# Sheet1.net
KiCad netlist of a schematic drawn in Altium Designer
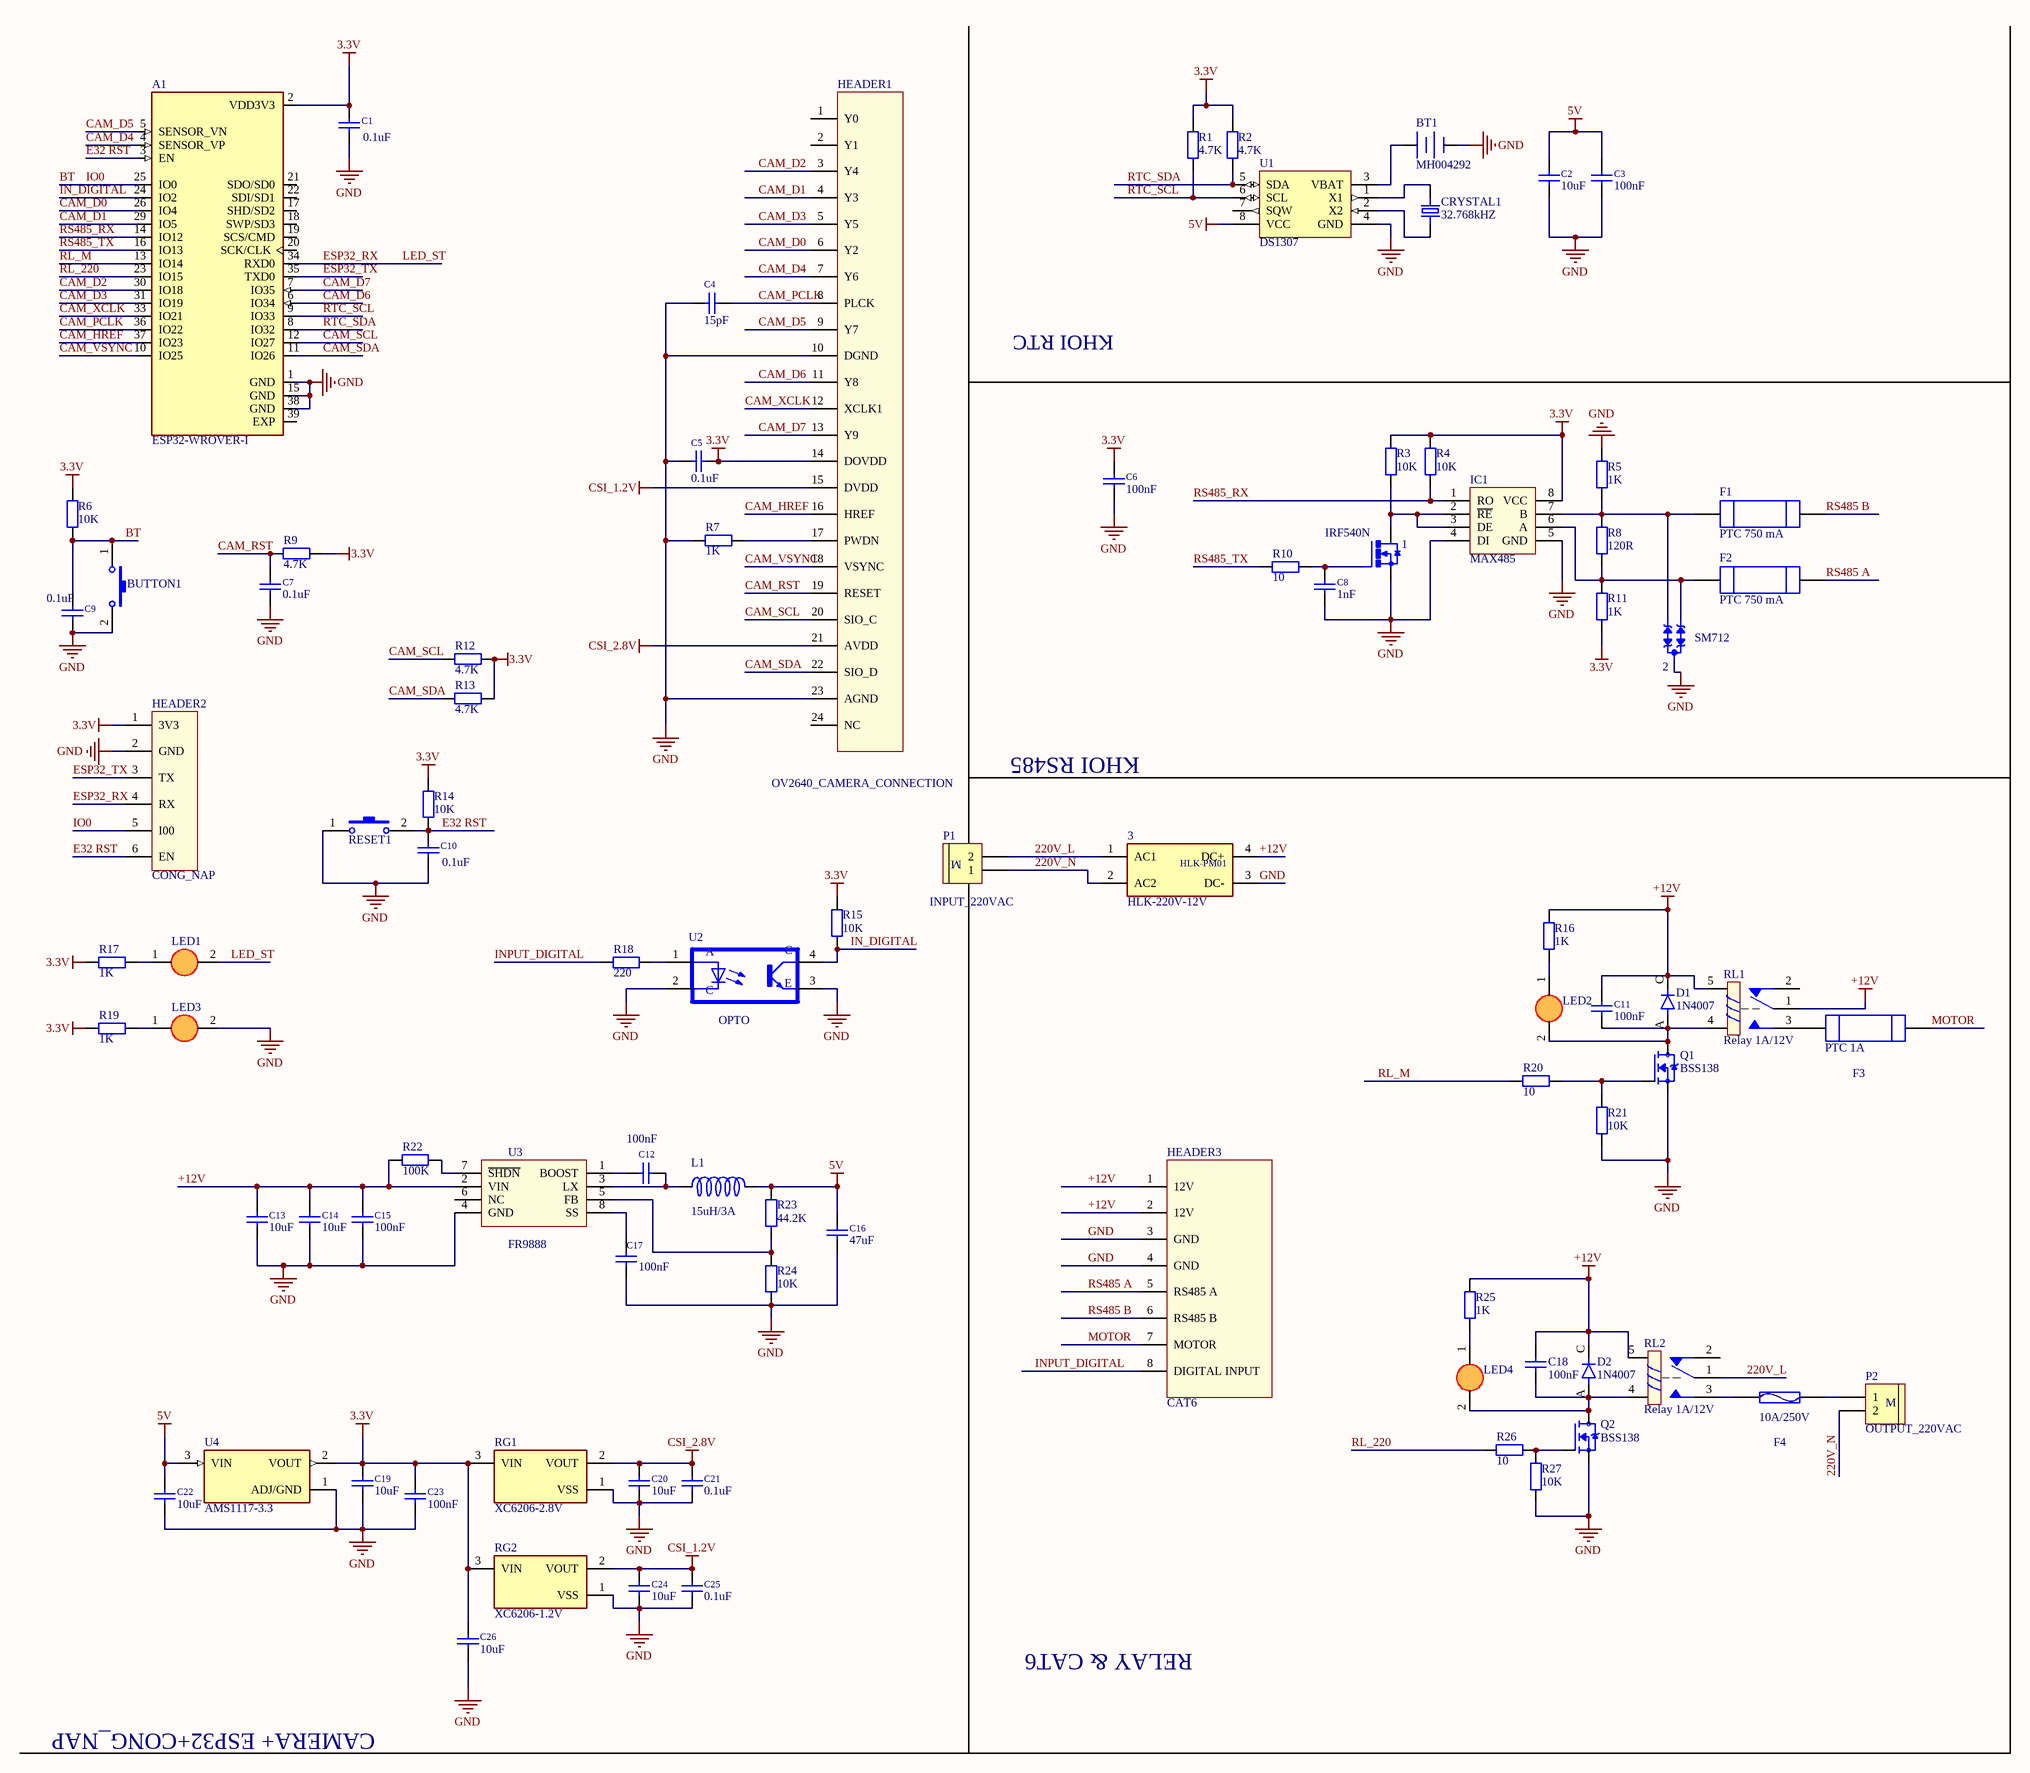
[diagram p0: Sheet1.SchDoc]

(export (version "E")
  (design (tool "Eeschema 10.0.6"))
  (components
    (comp (ref "1")
      (value "IRF540N")
      (footprint "D2PACK")
      (description "N-Channel 100V 33A _Tc_ 130W _Tc_ Surface Mount D2PAK")
      (fields (field (name "MF") "Infineon Technologies"))
      (libsource (lib "IRF540N") (part "IRF540N"))
    )
    (comp (ref "2")
      (value "SM712")
      (footprint "SOT23-3")
      (description "26V, 14V Clamp 17A _8/20Âµs_ Ipp Tvs Diode Surface Mount SOT-23-3")
      (fields (field (name "MP") "CDSOT23-SM712") (field (name "MF") "Bourns"))
      (libsource (lib "CDSOT23-SM712") (part "CDSOT23-SM712"))
    )
    (comp (ref "3")
      (value "HLK-220V-12V")
      (footprint "HLK 220-12")
      (fields (field (name "MF") "Hi-link") (field (name "MP") "hlk-pm01"))
      (libsource (lib "HLK-PM01") (part "HLK-PM01"))
    )
    (comp (ref "A1")
      (value "ESP32-WROVER-I")
      (footprint "XCVR_ESP32-WROVER-I")
      (fields (field (name "MF") "Espressif Systems"))
      (libsource (lib "ESP32-WROVER-I") (part "ESP32-WROVER-I"))
    )
    (comp (ref "BT1")
      (value "MH004292")
      (footprint "DE PINCR1220")
      (description "Dán")
      (libsource (lib "THU VIEN SCH") (part "De Pin 3.3V"))
    )
    (comp (ref "BUTTON1")
      (value "SW-2P-S")
      (footprint "BUTTON_4_PIN")
      (description "Switch Small 2 Pin")
      (fields (field (name "PUBLISHER") "Altium Limited"))
      (libsource (lib "Schematic") (part "SW-2PIN-SMALL"))
    )
    (comp (ref "C1")
      (value "0.1uF")
      (footprint "Tu 0603")
      (description "Capacitor")
      (fields (field (name "PUBLISHER") "Hoang Nguyen"))
      (libsource (lib "hphonglib") (part "Capacitor"))
    )
    (comp (ref "C2")
      (value "10uF")
      (footprint "C1210")
      (description "Capacitor")
      (fields (field (name "PUBLISHER") "Hoang Nguyen"))
      (libsource (lib "hphonglib") (part "Capacitor"))
    )
    (comp (ref "C3")
      (value "100nF")
      (footprint "Tu 0603")
      (description "Capacitor")
      (fields (field (name "PUBLISHER") "Hoang Nguyen"))
      (libsource (lib "hphonglib") (part "Capacitor"))
    )
    (comp (ref "C4")
      (value "15pF")
      (footprint "Tu 0603")
      (description "Capacitor")
      (fields (field (name "PUBLISHER") "Hoang Nguyen"))
      (libsource (lib "hphonglib") (part "Capacitor"))
    )
    (comp (ref "C5")
      (value "0.1uF")
      (footprint "Tu 0603")
      (description "Capacitor")
      (fields (field (name "PUBLISHER") "Hoang Nguyen"))
      (libsource (lib "hphonglib") (part "Capacitor"))
    )
    (comp (ref "C6")
      (value "100nF")
      (footprint "Tu 0603")
      (description "Capacitor")
      (fields (field (name "PUBLISHER") "Hoang Nguyen"))
      (libsource (lib "hphonglib") (part "Capacitor"))
    )
    (comp (ref "C7")
      (value "0.1uF")
      (footprint "Tu 0603")
      (description "Capacitor")
      (fields (field (name "PUBLISHER") "Hoang Nguyen"))
      (libsource (lib "hphonglib") (part "Capacitor"))
    )
    (comp (ref "C8")
      (value "1nF")
      (footprint "Tu 0603")
      (description "Capacitor")
      (fields (field (name "PUBLISHER") "Hoang Nguyen"))
      (libsource (lib "hphonglib") (part "Capacitor"))
    )
    (comp (ref "C9")
      (value "0.1uF")
      (footprint "Tu 0603")
      (description "Capacitor")
      (fields (field (name "PUBLISHER") "Hoang Nguyen"))
      (libsource (lib "hphonglib") (part "Capacitor"))
    )
    (comp (ref "C10")
      (value "0.1uF")
      (footprint "Tu 0603")
      (description "Capacitor")
      (fields (field (name "PUBLISHER") "Hoang Nguyen"))
      (libsource (lib "hphonglib") (part "Capacitor"))
    )
    (comp (ref "C11")
      (value "100nF")
      (footprint "Tu 0603")
      (description "Capacitor")
      (fields (field (name "PUBLISHER") "Hoang Nguyen"))
      (libsource (lib "hphonglib") (part "Capacitor"))
    )
    (comp (ref "C12")
      (value "100nF")
      (footprint "Tu 0603")
      (description "Capacitor")
      (fields (field (name "PUBLISHER") "Hoang Nguyen"))
      (libsource (lib "hphonglib") (part "Capacitor"))
    )
    (comp (ref "C13")
      (value "10uF")
      (footprint "C1210")
      (description "Capacitor")
      (fields (field (name "PUBLISHER") "Hoang Nguyen"))
      (libsource (lib "hphonglib") (part "Capacitor"))
    )
    (comp (ref "C14")
      (value "10uF")
      (footprint "C1210")
      (description "Capacitor")
      (fields (field (name "PUBLISHER") "Hoang Nguyen"))
      (libsource (lib "hphonglib") (part "Capacitor"))
    )
    (comp (ref "C15")
      (value "100nF")
      (footprint "Tu 0603")
      (description "Capacitor")
      (fields (field (name "PUBLISHER") "Hoang Nguyen"))
      (libsource (lib "hphonglib") (part "Capacitor"))
    )
    (comp (ref "C16")
      (value "47uF")
      (footprint "C1210")
      (description "Capacitor")
      (fields (field (name "PUBLISHER") "Hoang Nguyen"))
      (libsource (lib "hphonglib") (part "Capacitor"))
    )
    (comp (ref "C17")
      (value "100nF")
      (footprint "Tu 0603")
      (description "Capacitor")
      (fields (field (name "PUBLISHER") "Hoang Nguyen"))
      (libsource (lib "hphonglib") (part "Capacitor"))
    )
    (comp (ref "C18")
      (value "100nF")
      (footprint "Tu 0603")
      (libsource (lib "Schematic") (part "Cap SMD 1206"))
    )
    (comp (ref "C19")
      (value "10uF")
      (footprint "C1210")
      (description "Capacitor")
      (fields (field (name "PUBLISHER") "Hoang Nguyen"))
      (libsource (lib "hphonglib") (part "Capacitor"))
    )
    (comp (ref "C20")
      (value "10uF")
      (footprint "C1210")
      (description "Capacitor")
      (fields (field (name "PUBLISHER") "Hoang Nguyen"))
      (libsource (lib "hphonglib") (part "Capacitor"))
    )
    (comp (ref "C21")
      (value "0.1uF")
      (footprint "Tu 0603")
      (description "Capacitor")
      (fields (field (name "PUBLISHER") "Hoang Nguyen"))
      (libsource (lib "hphonglib") (part "Capacitor"))
    )
    (comp (ref "C22")
      (value "10uF")
      (footprint "C1210")
      (description "Capacitor")
      (fields (field (name "PUBLISHER") "Hoang Nguyen"))
      (libsource (lib "hphonglib") (part "Capacitor"))
    )
    (comp (ref "C23")
      (value "100nF")
      (footprint "Tu 0603")
      (description "Capacitor")
      (fields (field (name "PUBLISHER") "Hoang Nguyen"))
      (libsource (lib "hphonglib") (part "Capacitor"))
    )
    (comp (ref "C24")
      (value "10uF")
      (footprint "C1210")
      (description "Capacitor")
      (fields (field (name "PUBLISHER") "Hoang Nguyen"))
      (libsource (lib "hphonglib") (part "Capacitor"))
    )
    (comp (ref "C25")
      (value "0.1uF")
      (footprint "Tu 0603")
      (description "Capacitor")
      (fields (field (name "PUBLISHER") "Hoang Nguyen"))
      (libsource (lib "hphonglib") (part "Capacitor"))
    )
    (comp (ref "C26")
      (value "10uF")
      (footprint "C1210")
      (description "Capacitor")
      (fields (field (name "PUBLISHER") "Hoang Nguyen"))
      (libsource (lib "hphonglib") (part "Capacitor"))
    )
    (comp (ref "CRYSTAL1")
      (value "32.768kHZ")
      (footprint "XTAL_ABS07-32.768KHZ-T")
      (description "32.768kHz Â±20ppm Crystal 12.5pF 70 kOhms 2-SMD, No Lead")
      (fields (field (name "MF") "Abracon LLC") (field (name "MP") "ABS07-32.768KHZ"))
      (libsource (lib "ABS07-32.768KHZ-T") (part "ABS07-32.768KHZ-T"))
    )
    (comp (ref "D1")
      (value "1N4007")
      (footprint "DIOAD1060W80L520D270")
      (description "Diode Standard 1000V 1A Through Hole DO-204AL _DO-41_")
      (fields (field (name "MF") "ON Semiconductor"))
      (libsource (lib "1N4007") (part "1N4007"))
    )
    (comp (ref "D2")
      (value "1N4007")
      (footprint "DIOAD1060W80L520D270")
      (description "Diode Standard 1000V 1A Through Hole DO-204AL _DO-41_")
      (fields (field (name "MF") "ON Semiconductor"))
      (libsource (lib "1N4007") (part "1N4007"))
    )
    (comp (ref "F1")
      (value "PTC 750 mA")
      (footprint "1812")
      (description "Polymeric PTC Resettable Fuse 13.2V 750mA Ih Surface Mount 1812 _4532 Metric_, Concave")
      (fields (field (name "MP") "1812L075PR") (field (name "MF") "Littelfuse Inc."))
      (libsource (lib "PTC750mA") (part "1812L075PR"))
    )
    (comp (ref "F2")
      (value "PTC 750 mA")
      (footprint "1812")
      (description "Polymeric PTC Resettable Fuse 13.2V 750mA Ih Surface Mount 1812 _4532 Metric_, Concave")
      (fields (field (name "MP") "1812L075PR") (field (name "MF") "Littelfuse Inc."))
      (libsource (lib "PTC750mA") (part "1812L075PR"))
    )
    (comp (ref "F3")
      (value "PTC 1A")
      (footprint "1812")
      (description "Polymeric PTC Resettable Fuse 13.2V 750mA Ih Surface Mount 1812 _4532 Metric_, Concave")
      (fields (field (name "MP") "1812L075PR") (field (name "MF") "Littelfuse Inc."))
      (libsource (lib "PTC750mA") (part "1812L075PR"))
    )
    (comp (ref "F4")
      (value "10A/250V")
      (footprint "FUSE_10A")
      (description "Fuse")
      (fields (field (name "PUBLISHER") "Altium Limited"))
      (libsource (lib "Schematic") (part "Fuse 1"))
    )
    (comp (ref "HEADER1")
      (value "OV2640_CAMERA_CONNECTION")
      (footprint "OV2640_0.5mm")
      (description "OV2640_CAMERA")
      (libsource (lib "NGUYENVY08") (part "OV2640_CAMERA"))
    )
    (comp (ref "HEADER2")
      (value "CONG_NAP")
      (footprint "CONG_NAP")
      (libsource (lib "NGUYENVY08") (part "HEADER_6"))
    )
    (comp (ref "HEADER3")
      (value "CAT6")
      (footprint "CAT6_3.5mm")
      (libsource (lib "NGUYENVY08") (part "CAT6"))
    )
    (comp (ref "IC1")
      (value "MAX485")
      (footprint "SO-8")
      (description "RS232 - RS485 (Same sn75176)")
      (libsource (lib "syhaunguyen") (part "MAX485"))
    )
    (comp (ref "L1")
      (value "15uH/3A")
      (footprint "CUON CAM 200mil")
      (libsource (lib "Schematic") (part "Conductor"))
    )
    (comp (ref "LED1")
      (value "~")
      (footprint "LED_SMD_0603 - duplicate1")
      (description "LED 5mm")
      (libsource (lib "Schematic") (part "LED 5mm"))
    )
    (comp (ref "LED2")
      (value "~")
      (footprint "LED_SMD_0603 - duplicate1")
      (description "LED 5mm")
      (libsource (lib "Schematic") (part "LED 5mm"))
    )
    (comp (ref "LED3")
      (value "~")
      (footprint "LED_SMD_0603 - duplicate1")
      (description "LED 5mm")
      (libsource (lib "Schematic") (part "LED 5mm"))
    )
    (comp (ref "LED4")
      (value "~")
      (footprint "LED_SMD_0603 - duplicate1")
      (description "LED 5mm")
      (libsource (lib "Schematic") (part "LED 5mm"))
    )
    (comp (ref "P1")
      (value "INPUT_220VAC")
      (footprint "Medium - Header 2")
      (description "Header, 2-Pin, Medium")
      (fields (field (name "PUBLISHER") "Altium Limited"))
      (libsource (lib "Schematic") (part "Header 2 - M"))
    )
    (comp (ref "P2")
      (value "OUTPUT_220VAC")
      (footprint "Medium - Header 2")
      (description "Header, 2-Pin, Medium")
      (fields (field (name "PUBLISHER") "Altium Limited"))
      (libsource (lib "") (part "Header 2 - M_1"))
    )
    (comp (ref "Q1")
      (value "BSS138")
      (footprint "SOT95P240X111-3N")
      (description "N-Channel 50V 220mA (Ta) 360mW (Ta) Surface Mount SOT-23-3")
      (fields (field (name "MF") "MICROSS/On Semiconductor"))
      (libsource (lib "BSS138") (part "BSS138"))
    )
    (comp (ref "Q2")
      (value "BSS138")
      (footprint "SOT95P240X111-3N")
      (description "N-Channel 50V 220mA (Ta) 360mW (Ta) Surface Mount SOT-23-3")
      (fields (field (name "MF") "MICROSS/On Semiconductor"))
      (libsource (lib "BSS138") (part "BSS138"))
    )
    (comp (ref "R1")
      (value "4.7K")
      (footprint "TRO SMD 0603")
      (description "RES_08")
      (fields (field (name "PUBLISHER") "Altium Limited"))
      (libsource (lib "") (part "RES_08_1"))
    )
    (comp (ref "R2")
      (value "4.7K")
      (footprint "TRO SMD 0603")
      (description "RES_08")
      (fields (field (name "PUBLISHER") "Altium Limited"))
      (libsource (lib "") (part "RES_08_1"))
    )
    (comp (ref "R3")
      (value "10K")
      (footprint "TRO SMD 0603")
      (description "RES_08")
      (fields (field (name "PUBLISHER") "Altium Limited"))
      (libsource (lib "") (part "RES_08_1"))
    )
    (comp (ref "R4")
      (value "10K")
      (footprint "TRO SMD 0603")
      (description "RES_08")
      (fields (field (name "PUBLISHER") "Altium Limited"))
      (libsource (lib "") (part "RES_08_1"))
    )
    (comp (ref "R5")
      (value "1K")
      (footprint "TRO SMD 0603")
      (description "RES_08")
      (fields (field (name "PUBLISHER") "Altium Limited"))
      (libsource (lib "") (part "RES_08_1"))
    )
    (comp (ref "R6")
      (value "10K")
      (footprint "DIEN TRO 0805")
      (description "RES_08")
      (fields (field (name "PUBLISHER") "Altium Limited"))
      (libsource (lib "") (part "RES_08_1"))
    )
    (comp (ref "R7")
      (value "1K")
      (footprint "TRO SMD 0603")
      (description "RES_08")
      (fields (field (name "PUBLISHER") "Altium Limited"))
      (libsource (lib "Schematic") (part "RES_08"))
    )
    (comp (ref "R8")
      (value "120R")
      (footprint "TRO SMD 0603")
      (description "RES_08")
      (fields (field (name "PUBLISHER") "Altium Limited"))
      (libsource (lib "") (part "RES_08_1"))
    )
    (comp (ref "R9")
      (value "4.7K")
      (footprint "TRO SMD 0603")
      (description "RES_08")
      (fields (field (name "PUBLISHER") "Altium Limited"))
      (libsource (lib "Schematic") (part "RES_08"))
    )
    (comp (ref "R10")
      (value "10")
      (footprint "TRO SMD 0603")
      (description "RES_08")
      (fields (field (name "PUBLISHER") "Altium Limited"))
      (libsource (lib "") (part "RES_08_2"))
    )
    (comp (ref "R11")
      (value "1K")
      (footprint "TRO SMD 0603")
      (description "RES_08")
      (fields (field (name "PUBLISHER") "Altium Limited"))
      (libsource (lib "") (part "RES_08_1"))
    )
    (comp (ref "R12")
      (value "4.7K")
      (footprint "TRO SMD 0603")
      (description "RES_08")
      (fields (field (name "PUBLISHER") "Altium Limited"))
      (libsource (lib "Schematic") (part "RES_08"))
    )
    (comp (ref "R13")
      (value "4.7K")
      (footprint "TRO SMD 0603")
      (description "RES_08")
      (fields (field (name "PUBLISHER") "Altium Limited"))
      (libsource (lib "Schematic") (part "RES_08"))
    )
    (comp (ref "R14")
      (value "10K")
      (footprint "TRO SMD 0603")
      (description "RES_08")
      (fields (field (name "PUBLISHER") "Altium Limited"))
      (libsource (lib "") (part "RES_08_3"))
    )
    (comp (ref "R15")
      (value "10K")
      (footprint "TRO SMD 0603")
      (description "RES_08")
      (fields (field (name "PUBLISHER") "Altium Limited"))
      (libsource (lib "") (part "RES_08_1"))
    )
    (comp (ref "R16")
      (value "1K")
      (footprint "TRO SMD 0603")
      (description "RES_08")
      (fields (field (name "PUBLISHER") "Altium Limited"))
      (libsource (lib "") (part "RES_08_3"))
    )
    (comp (ref "R17")
      (value "1K")
      (footprint "TRO SMD 0603")
      (description "RES_08")
      (fields (field (name "PUBLISHER") "Altium Limited"))
      (libsource (lib "Schematic") (part "RES_08"))
    )
    (comp (ref "R18")
      (value "220")
      (footprint "TRO SMD 0603")
      (description "RES_08")
      (fields (field (name "PUBLISHER") "Altium Limited"))
      (libsource (lib "Schematic") (part "RES_08"))
    )
    (comp (ref "R19")
      (value "1K")
      (footprint "TRO SMD 0603")
      (description "RES_08")
      (fields (field (name "PUBLISHER") "Altium Limited"))
      (libsource (lib "Schematic") (part "RES_08"))
    )
    (comp (ref "R20")
      (value "10")
      (footprint "TRO SMD 0603")
      (description "RES_08")
      (fields (field (name "PUBLISHER") "Altium Limited"))
      (libsource (lib "") (part "RES_08_2"))
    )
    (comp (ref "R21")
      (value "10K")
      (footprint "TRO SMD 0603")
      (description "RES_08")
      (fields (field (name "PUBLISHER") "Altium Limited"))
      (libsource (lib "") (part "RES_08_1"))
    )
    (comp (ref "R22")
      (value "100K")
      (footprint "TRO SMD 0603")
      (description "RES_08")
      (fields (field (name "PUBLISHER") "Altium Limited"))
      (libsource (lib "Schematic") (part "RES_08"))
    )
    (comp (ref "R23")
      (value "44.2K")
      (footprint "DIEN TRO 0805")
      (description "RES_08")
      (fields (field (name "PUBLISHER") "Altium Limited"))
      (libsource (lib "") (part "RES_08_1"))
    )
    (comp (ref "R24")
      (value "10K")
      (footprint "TRO SMD 0603")
      (description "RES_08")
      (fields (field (name "PUBLISHER") "Altium Limited"))
      (libsource (lib "") (part "RES_08_1"))
    )
    (comp (ref "R25")
      (value "1K")
      (footprint "TRO SMD 0603")
      (description "RES_08")
      (fields (field (name "PUBLISHER") "Altium Limited"))
      (libsource (lib "") (part "RES_08_3"))
    )
    (comp (ref "R26")
      (value "10")
      (footprint "TRO SMD 0603")
      (description "RES_08")
      (fields (field (name "PUBLISHER") "Altium Limited"))
      (libsource (lib "") (part "RES_08_2"))
    )
    (comp (ref "R27")
      (value "10K")
      (footprint "TRO SMD 0603")
      (description "RES_08")
      (fields (field (name "PUBLISHER") "Altium Limited"))
      (libsource (lib "") (part "RES_08_1"))
    )
    (comp (ref "RESET1")
      (value "SW-2P-S")
      (footprint "BUTTON_4_PIN")
      (description "Switch Small 2 Pin")
      (fields (field (name "PUBLISHER") "Altium Limited"))
      (libsource (lib "Schematic") (part "SW-2PIN-SMALL"))
    )
    (comp (ref "RG1")
      (value "Reg_Torex_XC6206P332MR_eec")
      (footprint "Torex_https--www.torexsemi.com-file-SOT-23-SOT-23-pkg.pdf_0")
      (fields
        (field (name "PART NUMBER") "XC6206-2.8V")
        (field (name "VOLTAGE") "3.3V")
        (field (name "MANUFACTURER") "Torex")
        (field (name "MOUSER PART NUMBER") "865-XC6206P332MR-G")
      )
      (libsource (lib "Reg_Torex_XC6206P332MR_eec") (part "Reg_Torex_XC6206P332MR_eec"))
    )
    (comp (ref "RG2")
      (value "Reg_Torex_XC6206P332MR_eec")
      (footprint "Torex_https--www.torexsemi.com-file-SOT-23-SOT-23-pkg.pdf_0")
      (fields
        (field (name "PART NUMBER") "XC6206-1.2V")
        (field (name "VOLTAGE") "3.3V")
        (field (name "MANUFACTURER") "Torex")
        (field (name "MOUSER PART NUMBER") "865-XC6206P332MR-G")
      )
      (libsource (lib "Reg_Torex_XC6206P332MR_eec") (part "Reg_Torex_XC6206P332MR_eec"))
    )
    (comp (ref "RL1")
      (value "Relay 1A/12V")
      (footprint "RL_SPDT_10A")
      (description "Relay SPDT,10A - 12VDC 5 Pin")
      (libsource (lib "syhaunguyen") (part "Relay 1"))
    )
    (comp (ref "RL2")
      (value "Relay 1A/12V")
      (footprint "RL_SPDT_10A")
      (description "Relay SPDT,10A - 12VDC 5 Pin")
      (libsource (lib "syhaunguyen") (part "Relay 1"))
    )
    (comp (ref "U1")
      (value "DS1307")
      (footprint "SOIC8")
      (description "Realtime Clock IC")
      (fields (field (name "MANUFACTURER") "Maxim"))
      (libsource (lib "hphonglib") (part "DS1307"))
    )
    (comp (ref "U2")
      (value "OPTO")
      (footprint "SOIC254P1016X390-4N")
      (description "Optoisolator Transistor Output 5300Vrms 1 Channel 4-SMD")
      (fields (field (name "MF") "Vishay Semiconductor") (field (name "MP") "SFH615A-3X009T"))
      (libsource (lib "SFH615A-3X009T") (part "SFH615A-3X009T"))
    )
    (comp (ref "U3") (value "FR9888") (footprint "FR9888_SMD") (libsource (lib "NGUYENVY08") (part "FR9888")))
    (comp (ref "U4")
      (value "AMS1117-3.3")
      (footprint "SOT229P700X180-4N")
      (description "Sot223/Pkg 1-Amp 3.3-Volt Low Drop Out Voltage Regulatator")
      (fields (field (name "MF") "Advanced Monolithic Systems"))
      (libsource (lib "AMS1117-3.3") (part "AMS1117-3.3"))
    )
  )
  (nets
    (net (code "1") (name "+12V") (class "Default")
      (node (ref "3") (pin "4") (pinfunction "DC+_4") (pintype "power_in"))
      (node (ref "C11") (pin "1") (pinfunction "1_1") (pintype "passive"))
      (node (ref "C13") (pin "1") (pinfunction "1_1") (pintype "passive"))
      (node (ref "C14") (pin "1") (pinfunction "1_1") (pintype "passive"))
      (node (ref "C15") (pin "2") (pinfunction "2_2") (pintype "passive"))
      (node (ref "C18") (pin "2") (pinfunction "2_2") (pintype "passive"))
      (node (ref "D1") (pin "C") (pinfunction "C_C") (pintype "passive"))
      (node (ref "D2") (pin "C") (pinfunction "C_C") (pintype "passive"))
      (node (ref "HEADER3") (pin "1") (pinfunction "12V_1") (pintype "passive"))
      (node (ref "HEADER3") (pin "2") (pinfunction "12V_2") (pintype "passive"))
      (node (ref "R16") (pin "2") (pinfunction "2_2") (pintype "passive"))
      (node (ref "R22") (pin "2") (pinfunction "2_2") (pintype "passive"))
      (node (ref "R25") (pin "2") (pinfunction "2_2") (pintype "passive"))
      (node (ref "RL1") (pin "1") (pinfunction "1_1") (pintype "passive"))
      (node (ref "RL1") (pin "5") (pinfunction "5_5") (pintype "passive"))
      (node (ref "RL2") (pin "5") (pinfunction "5_5") (pintype "passive"))
      (node (ref "U3") (pin "2") (pinfunction "VIN_2") (pintype "passive"))
    )
    (net (code "2") (name "/220V_L") (class "Default")
      (node (ref "3") (pin "1") (pinfunction "AC1_1") (pintype "power_in"))
      (node (ref "P1") (pin "2") (pinfunction "2_2") (pintype "passive"))
      (node (ref "RL2") (pin "1") (pinfunction "1_1") (pintype "passive"))
    )
    (net (code "3") (name "/220V_N") (class "Default")
      (node (ref "3") (pin "2") (pinfunction "AC2_2") (pintype "power_in"))
      (node (ref "P1") (pin "1") (pinfunction "1_1") (pintype "passive"))
      (node (ref "P2") (pin "2") (pinfunction "2_2") (pintype "passive"))
    )
    (net (code "4") (name "/BT") (class "Default")
      (node (ref "A1") (pin "25") (pinfunction "IO0_25") (pintype "bidirectional"))
      (node (ref "BUTTON1") (pin "1") (pinfunction "1_1") (pintype "passive"))
      (node (ref "C9") (pin "1") (pinfunction "1_1") (pintype "passive"))
      (node (ref "HEADER2") (pin "5") (pinfunction "I00_5") (pintype "passive"))
      (node (ref "R6") (pin "2") (pinfunction "2_2") (pintype "passive"))
    )
    (net (code "5") (name "/CAM_D0") (class "Default")
      (node (ref "A1") (pin "26") (pinfunction "IO4_26") (pintype "bidirectional"))
      (node (ref "HEADER1") (pin "6") (pinfunction "Y2_6") (pintype "passive"))
    )
    (net (code "6") (name "/CAM_D1") (class "Default")
      (node (ref "A1") (pin "29") (pinfunction "IO5_29") (pintype "bidirectional"))
      (node (ref "HEADER1") (pin "4") (pinfunction "Y3_4") (pintype "passive"))
    )
    (net (code "7") (name "/CAM_D2") (class "Default")
      (node (ref "A1") (pin "30") (pinfunction "IO18_30") (pintype "bidirectional"))
      (node (ref "HEADER1") (pin "3") (pinfunction "Y4_3") (pintype "passive"))
    )
    (net (code "8") (name "/CAM_D3") (class "Default")
      (node (ref "A1") (pin "31") (pinfunction "IO19_31") (pintype "bidirectional"))
      (node (ref "HEADER1") (pin "5") (pinfunction "Y5_5") (pintype "passive"))
    )
    (net (code "9") (name "/CAM_D4") (class "Default")
      (node (ref "A1") (pin "4") (pinfunction "SENSOR_VP_4") (pintype "input"))
      (node (ref "HEADER1") (pin "7") (pinfunction "Y6_7") (pintype "passive"))
    )
    (net (code "10") (name "/CAM_D5") (class "Default")
      (node (ref "A1") (pin "5") (pinfunction "SENSOR_VN_5") (pintype "input"))
      (node (ref "HEADER1") (pin "9") (pinfunction "Y7_9") (pintype "passive"))
    )
    (net (code "11") (name "/CAM_D6") (class "Default")
      (node (ref "A1") (pin "6") (pinfunction "IO34_6") (pintype "input"))
      (node (ref "HEADER1") (pin "11") (pinfunction "Y8_11") (pintype "passive"))
    )
    (net (code "12") (name "/CAM_D7") (class "Default")
      (node (ref "A1") (pin "7") (pinfunction "IO35_7") (pintype "input"))
      (node (ref "HEADER1") (pin "13") (pinfunction "Y9_13") (pintype "passive"))
    )
    (net (code "13") (name "/CAM_HREF") (class "Default")
      (node (ref "A1") (pin "37") (pinfunction "IO23_37") (pintype "bidirectional"))
      (node (ref "HEADER1") (pin "16") (pinfunction "HREF_16") (pintype "passive"))
    )
    (net (code "14") (name "/CAM_PCLK") (class "Default")
      (node (ref "A1") (pin "36") (pinfunction "IO22_36") (pintype "bidirectional"))
      (node (ref "C4") (pin "2") (pinfunction "2_2") (pintype "passive"))
      (node (ref "HEADER1") (pin "8") (pinfunction "PLCK_8") (pintype "passive"))
    )
    (net (code "15") (name "/CAM_RST") (class "Default")
      (node (ref "C7") (pin "1") (pinfunction "1_1") (pintype "passive"))
      (node (ref "HEADER1") (pin "19") (pinfunction "RESET_19") (pintype "passive"))
      (node (ref "R9") (pin "2") (pinfunction "2_2") (pintype "passive"))
    )
    (net (code "16") (name "/CAM_SCL") (class "Default")
      (node (ref "A1") (pin "12") (pinfunction "IO27_12") (pintype "bidirectional"))
      (node (ref "HEADER1") (pin "20") (pinfunction "SIO_C_20") (pintype "passive"))
      (node (ref "R12") (pin "2") (pinfunction "2_2") (pintype "passive"))
    )
    (net (code "17") (name "/CAM_SDA") (class "Default")
      (node (ref "A1") (pin "11") (pinfunction "IO26_11") (pintype "bidirectional"))
      (node (ref "HEADER1") (pin "22") (pinfunction "SIO_D_22") (pintype "passive"))
      (node (ref "R13") (pin "2") (pinfunction "2_2") (pintype "passive"))
    )
    (net (code "18") (name "/CAM_VSYNC") (class "Default")
      (node (ref "A1") (pin "10") (pinfunction "IO25_10") (pintype "bidirectional"))
      (node (ref "HEADER1") (pin "18") (pinfunction "VSYNC_18") (pintype "passive"))
    )
    (net (code "19") (name "/CAM_XCLK") (class "Default")
      (node (ref "A1") (pin "33") (pinfunction "IO21_33") (pintype "bidirectional"))
      (node (ref "HEADER1") (pin "12") (pinfunction "XCLK1_12") (pintype "passive"))
    )
    (net (code "20") (name "/E32 RST") (class "Default")
      (node (ref "A1") (pin "3") (pinfunction "EN_3") (pintype "input"))
      (node (ref "C10") (pin "1") (pinfunction "1_1") (pintype "passive"))
      (node (ref "HEADER2") (pin "6") (pinfunction "EN_6") (pintype "passive"))
      (node (ref "R14") (pin "1") (pinfunction "1_1") (pintype "passive"))
      (node (ref "RESET1") (pin "2") (pinfunction "2_2") (pintype "passive"))
    )
    (net (code "21") (name "/ESP32_RX") (class "Default")
      (node (ref "A1") (pin "34") (pinfunction "RXD0_34") (pintype "bidirectional"))
      (node (ref "HEADER2") (pin "4") (pinfunction "RX_4") (pintype "passive"))
      (node (ref "LED1") (pin "2") (pinfunction "K_2") (pintype "passive"))
    )
    (net (code "22") (name "/ESP32_TX") (class "Default")
      (node (ref "A1") (pin "35") (pinfunction "TXD0_35") (pintype "bidirectional"))
      (node (ref "HEADER2") (pin "3") (pinfunction "TX_3") (pintype "passive"))
    )
    (net (code "23") (name "/INPUT_DIGITAL") (class "Default")
      (node (ref "HEADER3") (pin "8") (pinfunction "DIGITAL_INPUT_8") (pintype "passive"))
      (node (ref "R18") (pin "2") (pinfunction "2_2") (pintype "passive"))
    )
    (net (code "24") (name "/IN_DIGITAL") (class "Default")
      (node (ref "A1") (pin "24") (pinfunction "IO2_24") (pintype "bidirectional"))
      (node (ref "R15") (pin "2") (pinfunction "2_2") (pintype "passive"))
      (node (ref "U2") (pin "4") (pinfunction "CO_4") (pintype "passive"))
    )
    (net (code "25") (name "/MOTOR") (class "Default")
      (node (ref "F3") (pin "2") (pinfunction "2_2") (pintype "passive"))
      (node (ref "HEADER3") (pin "7") (pinfunction "MOTOR_7") (pintype "passive"))
    )
    (net (code "26") (name "/RL_220") (class "Default")
      (node (ref "A1") (pin "23") (pinfunction "IO15_23") (pintype "bidirectional"))
      (node (ref "R26") (pin "1") (pinfunction "1_1") (pintype "passive"))
    )
    (net (code "27") (name "/RL_M") (class "Default")
      (node (ref "A1") (pin "13") (pinfunction "IO14_13") (pintype "bidirectional"))
      (node (ref "R20") (pin "1") (pinfunction "1_1") (pintype "passive"))
    )
    (net (code "28") (name "/RS485 A") (class "Default")
      (node (ref "F2") (pin "2") (pinfunction "2_2") (pintype "passive"))
      (node (ref "HEADER3") (pin "5") (pinfunction "RS485_A_5") (pintype "passive"))
    )
    (net (code "29") (name "/RS485 B") (class "Default")
      (node (ref "F1") (pin "2") (pinfunction "2_2") (pintype "passive"))
      (node (ref "HEADER3") (pin "6") (pinfunction "RS485_B_6") (pintype "passive"))
    )
    (net (code "30") (name "/RS485_RX") (class "Default")
      (node (ref "A1") (pin "14") (pinfunction "IO12_14") (pintype "bidirectional"))
      (node (ref "IC1") (pin "1") (pinfunction "RO_1") (pintype "passive"))
      (node (ref "R4") (pin "2") (pinfunction "2_2") (pintype "passive"))
    )
    (net (code "31") (name "/RS485_TX") (class "Default")
      (node (ref "A1") (pin "16") (pinfunction "IO13_16") (pintype "bidirectional"))
      (node (ref "R10") (pin "1") (pinfunction "1_1") (pintype "passive"))
    )
    (net (code "32") (name "/RTC_SCL") (class "Default")
      (node (ref "A1") (pin "9") (pinfunction "IO33_9") (pintype "bidirectional"))
      (node (ref "R1") (pin "2") (pinfunction "2_2") (pintype "passive"))
      (node (ref "U1") (pin "6") (pinfunction "SCL_6") (pintype "bidirectional"))
    )
    (net (code "33") (name "/RTC_SDA") (class "Default")
      (node (ref "A1") (pin "8") (pinfunction "IO32_8") (pintype "bidirectional"))
      (node (ref "R2") (pin "2") (pinfunction "2_2") (pintype "passive"))
      (node (ref "U1") (pin "5") (pinfunction "SDA_5") (pintype "bidirectional"))
    )
    (net (code "34") (name "3.3V") (class "Default")
      (node (ref "A1") (pin "2") (pinfunction "VDD3V3_2") (pintype "power_in"))
      (node (ref "C1") (pin "1") (pinfunction "1_1") (pintype "passive"))
      (node (ref "C19") (pin "1") (pinfunction "1_1") (pintype "passive"))
      (node (ref "C23") (pin "1") (pinfunction "1_1") (pintype "passive"))
      (node (ref "C26") (pin "1") (pinfunction "1_1") (pintype "passive"))
      (node (ref "C5") (pin "2") (pinfunction "2_2") (pintype "passive"))
      (node (ref "C6") (pin "1") (pinfunction "1_1") (pintype "passive"))
      (node (ref "HEADER1") (pin "14") (pinfunction "DOVDD_14") (pintype "passive"))
      (node (ref "HEADER2") (pin "1") (pinfunction "3V3_1") (pintype "passive"))
      (node (ref "IC1") (pin "8") (pinfunction "VCC_8") (pintype "passive"))
      (node (ref "R1") (pin "1") (pinfunction "1_1") (pintype "passive"))
      (node (ref "R11") (pin "2") (pinfunction "2_2") (pintype "passive"))
      (node (ref "R12") (pin "1") (pinfunction "1_1") (pintype "passive"))
      (node (ref "R13") (pin "1") (pinfunction "1_1") (pintype "passive"))
      (node (ref "R14") (pin "2") (pinfunction "2_2") (pintype "passive"))
      (node (ref "R15") (pin "1") (pinfunction "1_1") (pintype "passive"))
      (node (ref "R17") (pin "2") (pinfunction "2_2") (pintype "passive"))
      (node (ref "R19") (pin "2") (pinfunction "2_2") (pintype "passive"))
      (node (ref "R2") (pin "1") (pinfunction "1_1") (pintype "passive"))
      (node (ref "R3") (pin "1") (pinfunction "1_1") (pintype "passive"))
      (node (ref "R4") (pin "1") (pinfunction "1_1") (pintype "passive"))
      (node (ref "R6") (pin "1") (pinfunction "1_1") (pintype "passive"))
      (node (ref "R9") (pin "1") (pinfunction "1_1") (pintype "passive"))
      (node (ref "RG1") (pin "3") (pinfunction "VIN_3") (pintype "passive"))
      (node (ref "RG2") (pin "3") (pinfunction "VIN_3") (pintype "passive"))
      (node (ref "U4") (pin "2") (pinfunction "VOUT_2") (pintype "output"))
    )
    (net (code "35") (name "5V") (class "Default")
      (node (ref "C16") (pin "1") (pinfunction "1_1") (pintype "passive"))
      (node (ref "C2") (pin "1") (pinfunction "1_1") (pintype "passive"))
      (node (ref "C22") (pin "1") (pinfunction "1_1") (pintype "passive"))
      (node (ref "C3") (pin "1") (pinfunction "1_1") (pintype "passive"))
      (node (ref "L1") (pin "2") (pinfunction "2_2") (pintype "passive"))
      (node (ref "R23") (pin "1") (pinfunction "1_1") (pintype "passive"))
      (node (ref "U1") (pin "8") (pinfunction "VCC_8") (pintype "power_in"))
      (node (ref "U4") (pin "3") (pinfunction "VIN_3") (pintype "input"))
    )
    (net (code "36") (name "CSI_1.2V") (class "Default")
      (node (ref "C24") (pin "1") (pinfunction "1_1") (pintype "passive"))
      (node (ref "C25") (pin "1") (pinfunction "1_1") (pintype "passive"))
      (node (ref "HEADER1") (pin "15") (pinfunction "DVDD_15") (pintype "passive"))
      (node (ref "RG2") (pin "2") (pinfunction "VOUT_2") (pintype "passive"))
    )
    (net (code "37") (name "CSI_2.8V") (class "Default")
      (node (ref "C20") (pin "1") (pinfunction "1_1") (pintype "passive"))
      (node (ref "C21") (pin "1") (pinfunction "1_1") (pintype "passive"))
      (node (ref "HEADER1") (pin "21") (pinfunction "AVDD_21") (pintype "passive"))
      (node (ref "RG1") (pin "2") (pinfunction "VOUT_2") (pintype "passive"))
    )
    (net (code "38") (name "GND") (class "Default")
      (node (ref "1") (pin "3") (pinfunction "S_3") (pintype "passive"))
      (node (ref "2") (pin "3") (pinfunction "P$3_3") (pintype "passive"))
      (node (ref "3") (pin "3") (pinfunction "DC-_3") (pintype "power_in"))
      (node (ref "A1") (pin "1") (pinfunction "GND_1") (pintype "power_in"))
      (node (ref "A1") (pin "15") (pinfunction "GND_15") (pintype "power_in"))
      (node (ref "A1") (pin "38") (pinfunction "GND_38") (pintype "power_in"))
      (node (ref "BT1") (pin "2") (pinfunction "-_2") (pintype "passive"))
      (node (ref "BUTTON1") (pin "2") (pinfunction "2_2") (pintype "passive"))
      (node (ref "C1") (pin "2") (pinfunction "2_2") (pintype "passive"))
      (node (ref "C10") (pin "2") (pinfunction "2_2") (pintype "passive"))
      (node (ref "C13") (pin "2") (pinfunction "2_2") (pintype "passive"))
      (node (ref "C14") (pin "2") (pinfunction "2_2") (pintype "passive"))
      (node (ref "C15") (pin "1") (pinfunction "1_1") (pintype "passive"))
      (node (ref "C16") (pin "2") (pinfunction "2_2") (pintype "passive"))
      (node (ref "C17") (pin "2") (pinfunction "2_2") (pintype "passive"))
      (node (ref "C19") (pin "2") (pinfunction "2_2") (pintype "passive"))
      (node (ref "C2") (pin "2") (pinfunction "2_2") (pintype "passive"))
      (node (ref "C20") (pin "2") (pinfunction "2_2") (pintype "passive"))
      (node (ref "C21") (pin "2") (pinfunction "2_2") (pintype "passive"))
      (node (ref "C22") (pin "2") (pinfunction "2_2") (pintype "passive"))
      (node (ref "C23") (pin "2") (pinfunction "2_2") (pintype "passive"))
      (node (ref "C24") (pin "2") (pinfunction "2_2") (pintype "passive"))
      (node (ref "C25") (pin "2") (pinfunction "2_2") (pintype "passive"))
      (node (ref "C26") (pin "2") (pinfunction "2_2") (pintype "passive"))
      (node (ref "C3") (pin "2") (pinfunction "2_2") (pintype "passive"))
      (node (ref "C4") (pin "1") (pinfunction "1_1") (pintype "passive"))
      (node (ref "C5") (pin "1") (pinfunction "1_1") (pintype "passive"))
      (node (ref "C6") (pin "2") (pinfunction "2_2") (pintype "passive"))
      (node (ref "C7") (pin "2") (pinfunction "2_2") (pintype "passive"))
      (node (ref "C8") (pin "2") (pinfunction "2_2") (pintype "passive"))
      (node (ref "C9") (pin "2") (pinfunction "2_2") (pintype "passive"))
      (node (ref "HEADER1") (pin "10") (pinfunction "DGND_10") (pintype "passive"))
      (node (ref "HEADER1") (pin "23") (pinfunction "AGND_23") (pintype "passive"))
      (node (ref "HEADER2") (pin "2") (pinfunction "GND_2") (pintype "passive"))
      (node (ref "HEADER3") (pin "3") (pinfunction "GND_3") (pintype "passive"))
      (node (ref "HEADER3") (pin "4") (pinfunction "GND_4") (pintype "passive"))
      (node (ref "IC1") (pin "4") (pinfunction "DI_4") (pintype "passive"))
      (node (ref "IC1") (pin "5") (pinfunction "GND_5") (pintype "passive"))
      (node (ref "LED3") (pin "2") (pinfunction "K_2") (pintype "passive"))
      (node (ref "Q1") (pin "2") (pinfunction "S_2") (pintype "passive"))
      (node (ref "Q2") (pin "2") (pinfunction "S_2") (pintype "passive"))
      (node (ref "R21") (pin "2") (pinfunction "2_2") (pintype "passive"))
      (node (ref "R24") (pin "2") (pinfunction "2_2") (pintype "passive"))
      (node (ref "R27") (pin "2") (pinfunction "2_2") (pintype "passive"))
      (node (ref "R5") (pin "1") (pinfunction "1_1") (pintype "passive"))
      (node (ref "R7") (pin "2") (pinfunction "2_2") (pintype "passive"))
      (node (ref "RESET1") (pin "1") (pinfunction "1_1") (pintype "passive"))
      (node (ref "RG1") (pin "1") (pinfunction "VSS_1") (pintype "passive"))
      (node (ref "RG2") (pin "1") (pinfunction "VSS_1") (pintype "passive"))
      (node (ref "U1") (pin "4") (pinfunction "GND_4") (pintype "power_in"))
      (node (ref "U2") (pin "2") (pinfunction "C_2") (pintype "passive"))
      (node (ref "U2") (pin "3") (pinfunction "E_3") (pintype "passive"))
      (node (ref "U3") (pin "4") (pinfunction "GND_4") (pintype "passive"))
      (node (ref "U4") (pin "1") (pinfunction "ADJ/GND_1") (pintype "power_in"))
    )
    (net (code "39") (name "Net-(1-D)") (class "Default")
      (node (ref "1") (pin "2") (pinfunction "D_2") (pintype "passive"))
      (node (ref "IC1") (pin "2") (pinfunction "~{RE}_2") (pintype "passive"))
      (node (ref "IC1") (pin "3") (pinfunction "DE_3") (pintype "passive"))
      (node (ref "R3") (pin "2") (pinfunction "2_2") (pintype "passive"))
    )
    (net (code "40") (name "Net-(1-G)") (class "Default")
      (node (ref "1") (pin "1") (pinfunction "G_1") (pintype "passive"))
      (node (ref "C8") (pin "1") (pinfunction "1_1") (pintype "passive"))
      (node (ref "R10") (pin "2") (pinfunction "2_2") (pintype "passive"))
    )
    (net (code "41") (name "Net-(2-P$1)") (class "Default")
      (node (ref "2") (pin "1") (pinfunction "P$1_1") (pintype "passive"))
      (node (ref "F2") (pin "1") (pinfunction "1_1") (pintype "passive"))
      (node (ref "IC1") (pin "6") (pinfunction "A_6") (pintype "passive"))
      (node (ref "R11") (pin "1") (pinfunction "1_1") (pintype "passive"))
      (node (ref "R8") (pin "2") (pinfunction "2_2") (pintype "passive"))
    )
    (net (code "42") (name "Net-(2-P$2)") (class "Default")
      (node (ref "2") (pin "2") (pinfunction "P$2_2") (pintype "passive"))
      (node (ref "F1") (pin "1") (pinfunction "1_1") (pintype "passive"))
      (node (ref "IC1") (pin "7") (pinfunction "B_7") (pintype "passive"))
      (node (ref "R5") (pin "2") (pinfunction "2_2") (pintype "passive"))
      (node (ref "R8") (pin "1") (pinfunction "1_1") (pintype "passive"))
    )
    (net (code "43") (name "Net-(BT1-+)") (class "Default")
      (node (ref "BT1") (pin "1") (pinfunction "+_1") (pintype "passive"))
      (node (ref "U1") (pin "3") (pinfunction "VBAT_3") (pintype "power_in"))
    )
    (net (code "44") (name "Net-(F3-Pad1)") (class "Default")
      (node (ref "F3") (pin "1") (pinfunction "1_1") (pintype "passive"))
      (node (ref "RL1") (pin "3") (pinfunction "3_3") (pintype "passive"))
    )
    (net (code "45") (name "Net-(F4-Pad1)") (class "Default")
      (node (ref "F4") (pin "1") (pinfunction "1_1") (pintype "passive"))
      (node (ref "RL2") (pin "3") (pinfunction "3_3") (pintype "passive"))
    )
    (net (code "46") (name "Net-(F4-Pad2)") (class "Default")
      (node (ref "F4") (pin "2") (pinfunction "2_2") (pintype "passive"))
      (node (ref "P2") (pin "1") (pinfunction "1_1") (pintype "passive"))
    )
    (net (code "47") (name "Net-(HEADER1-PWDN)") (class "Default")
      (node (ref "HEADER1") (pin "17") (pinfunction "PWDN_17") (pintype "passive"))
      (node (ref "R7") (pin "1") (pinfunction "1_1") (pintype "passive"))
    )
    (net (code "48") (name "Net-(LED1-A)") (class "Default")
      (node (ref "LED1") (pin "1") (pinfunction "A_1") (pintype "passive"))
      (node (ref "R17") (pin "1") (pinfunction "1_1") (pintype "passive"))
    )
    (net (code "49") (name "Net-(LED2-A)") (class "Default")
      (node (ref "LED2") (pin "1") (pinfunction "A_1") (pintype "passive"))
      (node (ref "R16") (pin "1") (pinfunction "1_1") (pintype "passive"))
    )
    (net (code "50") (name "Net-(LED2-K)") (class "Default")
      (node (ref "C11") (pin "2") (pinfunction "2_2") (pintype "passive"))
      (node (ref "D1") (pin "A") (pinfunction "A_A") (pintype "passive"))
      (node (ref "LED2") (pin "2") (pinfunction "K_2") (pintype "passive"))
      (node (ref "Q1") (pin "3") (pinfunction "D_3") (pintype "passive"))
      (node (ref "RL1") (pin "4") (pinfunction "4_4") (pintype "passive"))
    )
    (net (code "51") (name "Net-(LED3-A)") (class "Default")
      (node (ref "LED3") (pin "1") (pinfunction "A_1") (pintype "passive"))
      (node (ref "R19") (pin "1") (pinfunction "1_1") (pintype "passive"))
    )
    (net (code "52") (name "Net-(LED4-A)") (class "Default")
      (node (ref "LED4") (pin "1") (pinfunction "A_1") (pintype "passive"))
      (node (ref "R25") (pin "1") (pinfunction "1_1") (pintype "passive"))
    )
    (net (code "53") (name "Net-(LED4-K)") (class "Default")
      (node (ref "C18") (pin "1") (pinfunction "1_1") (pintype "passive"))
      (node (ref "D2") (pin "A") (pinfunction "A_A") (pintype "passive"))
      (node (ref "LED4") (pin "2") (pinfunction "K_2") (pintype "passive"))
      (node (ref "Q2") (pin "3") (pinfunction "D_3") (pintype "passive"))
      (node (ref "RL2") (pin "4") (pinfunction "4_4") (pintype "passive"))
    )
    (net (code "54") (name "Net-(Q1-G)") (class "Default")
      (node (ref "Q1") (pin "1") (pinfunction "G_1") (pintype "passive"))
      (node (ref "R20") (pin "2") (pinfunction "2_2") (pintype "passive"))
      (node (ref "R21") (pin "1") (pinfunction "1_1") (pintype "passive"))
    )
    (net (code "55") (name "Net-(Q2-G)") (class "Default")
      (node (ref "Q2") (pin "1") (pinfunction "G_1") (pintype "passive"))
      (node (ref "R26") (pin "2") (pinfunction "2_2") (pintype "passive"))
      (node (ref "R27") (pin "1") (pinfunction "1_1") (pintype "passive"))
    )
    (net (code "56") (name "Net-(U1-X1)") (class "Default")
      (node (ref "CRYSTAL1") (pin "2") (pinfunction "2_2") (pintype "passive"))
      (node (ref "U1") (pin "1") (pinfunction "X1_1") (pintype "output"))
    )
    (net (code "57") (name "Net-(U1-X2)") (class "Default")
      (node (ref "CRYSTAL1") (pin "1") (pinfunction "1_1") (pintype "passive"))
      (node (ref "U1") (pin "2") (pinfunction "X2_2") (pintype "input"))
    )
    (net (code "58") (name "Net-(U2-A)") (class "Default")
      (node (ref "R18") (pin "1") (pinfunction "1_1") (pintype "passive"))
      (node (ref "U2") (pin "1") (pinfunction "A_1") (pintype "passive"))
    )
    (net (code "59") (name "Net-(U3-BOOST)") (class "Default")
      (node (ref "C12") (pin "1") (pinfunction "1_1") (pintype "passive"))
      (node (ref "U3") (pin "1") (pinfunction "BOOST_1") (pintype "passive"))
    )
    (net (code "60") (name "Net-(U3-FB)") (class "Default")
      (node (ref "R23") (pin "2") (pinfunction "2_2") (pintype "passive"))
      (node (ref "R24") (pin "1") (pinfunction "1_1") (pintype "passive"))
      (node (ref "U3") (pin "5") (pinfunction "FB_5") (pintype "passive"))
    )
    (net (code "61") (name "Net-(U3-LX)") (class "Default")
      (node (ref "C12") (pin "2") (pinfunction "2_2") (pintype "passive"))
      (node (ref "L1") (pin "1") (pinfunction "1_1") (pintype "passive"))
      (node (ref "U3") (pin "3") (pinfunction "LX_3") (pintype "passive"))
    )
    (net (code "62") (name "Net-(U3-SS)") (class "Default")
      (node (ref "C17") (pin "1") (pinfunction "1_1") (pintype "passive"))
      (node (ref "U3") (pin "8") (pinfunction "SS_8") (pintype "passive"))
    )
    (net (code "63") (name "Net-(U3-~{SHDN})") (class "Default")
      (node (ref "R22") (pin "1") (pinfunction "1_1") (pintype "passive"))
      (node (ref "U3") (pin "7") (pinfunction "~{SHDN}_7") (pintype "passive"))
    )
    (net (code "64") (name "unconnected-(A1-EXP-Pad39)") (class "Default")
      (node (ref "A1") (pin "39") (pinfunction "EXP_39") (pintype "power_in"))
    )
    (net (code "65") (name "unconnected-(A1-SCK{slash}CLK-Pad20)") (class "Default")
      (node (ref "A1") (pin "20") (pinfunction "SCK/CLK_20") (pintype "bidirectional"))
    )
    (net (code "66") (name "unconnected-(A1-SCS{slash}CMD-Pad19)") (class "Default")
      (node (ref "A1") (pin "19") (pinfunction "SCS/CMD_19") (pintype "bidirectional"))
    )
    (net (code "67") (name "unconnected-(A1-SDI{slash}SD1-Pad22)") (class "Default")
      (node (ref "A1") (pin "22") (pinfunction "SDI/SD1_22") (pintype "bidirectional"))
    )
    (net (code "68") (name "unconnected-(A1-SDO{slash}SD0-Pad21)") (class "Default")
      (node (ref "A1") (pin "21") (pinfunction "SDO/SD0_21") (pintype "bidirectional"))
    )
    (net (code "69") (name "unconnected-(A1-SHD{slash}SD2-Pad17)") (class "Default")
      (node (ref "A1") (pin "17") (pinfunction "SHD/SD2_17") (pintype "bidirectional"))
    )
    (net (code "70") (name "unconnected-(A1-SWP{slash}SD3-Pad18)") (class "Default")
      (node (ref "A1") (pin "18") (pinfunction "SWP/SD3_18") (pintype "bidirectional"))
    )
    (net (code "71") (name "unconnected-(HEADER1-NC-Pad24)") (class "Default")
      (node (ref "HEADER1") (pin "24") (pinfunction "NC_24") (pintype "passive"))
    )
    (net (code "72") (name "unconnected-(HEADER1-Y0-Pad1)") (class "Default")
      (node (ref "HEADER1") (pin "1") (pinfunction "Y0_1") (pintype "passive"))
    )
    (net (code "73") (name "unconnected-(HEADER1-Y1-Pad2)") (class "Default")
      (node (ref "HEADER1") (pin "2") (pinfunction "Y1_2") (pintype "passive"))
    )
    (net (code "74") (name "unconnected-(RL1-Pad2)") (class "Default")
      (node (ref "RL1") (pin "2") (pinfunction "2_2") (pintype "passive"))
    )
    (net (code "75") (name "unconnected-(RL2-Pad2)") (class "Default")
      (node (ref "RL2") (pin "2") (pinfunction "2_2") (pintype "passive"))
    )
    (net (code "76") (name "unconnected-(U1-SQW-Pad7)") (class "Default")
      (node (ref "U1") (pin "7") (pinfunction "SQW_7") (pintype "output"))
    )
    (net (code "77") (name "unconnected-(U3-NC-Pad6)") (class "Default")
      (node (ref "U3") (pin "6") (pinfunction "NC_6") (pintype "passive"))
    )
  )
)
